# OpenBook_Schematic.net
KiCad netlist of a schematic drawn in EAGLE
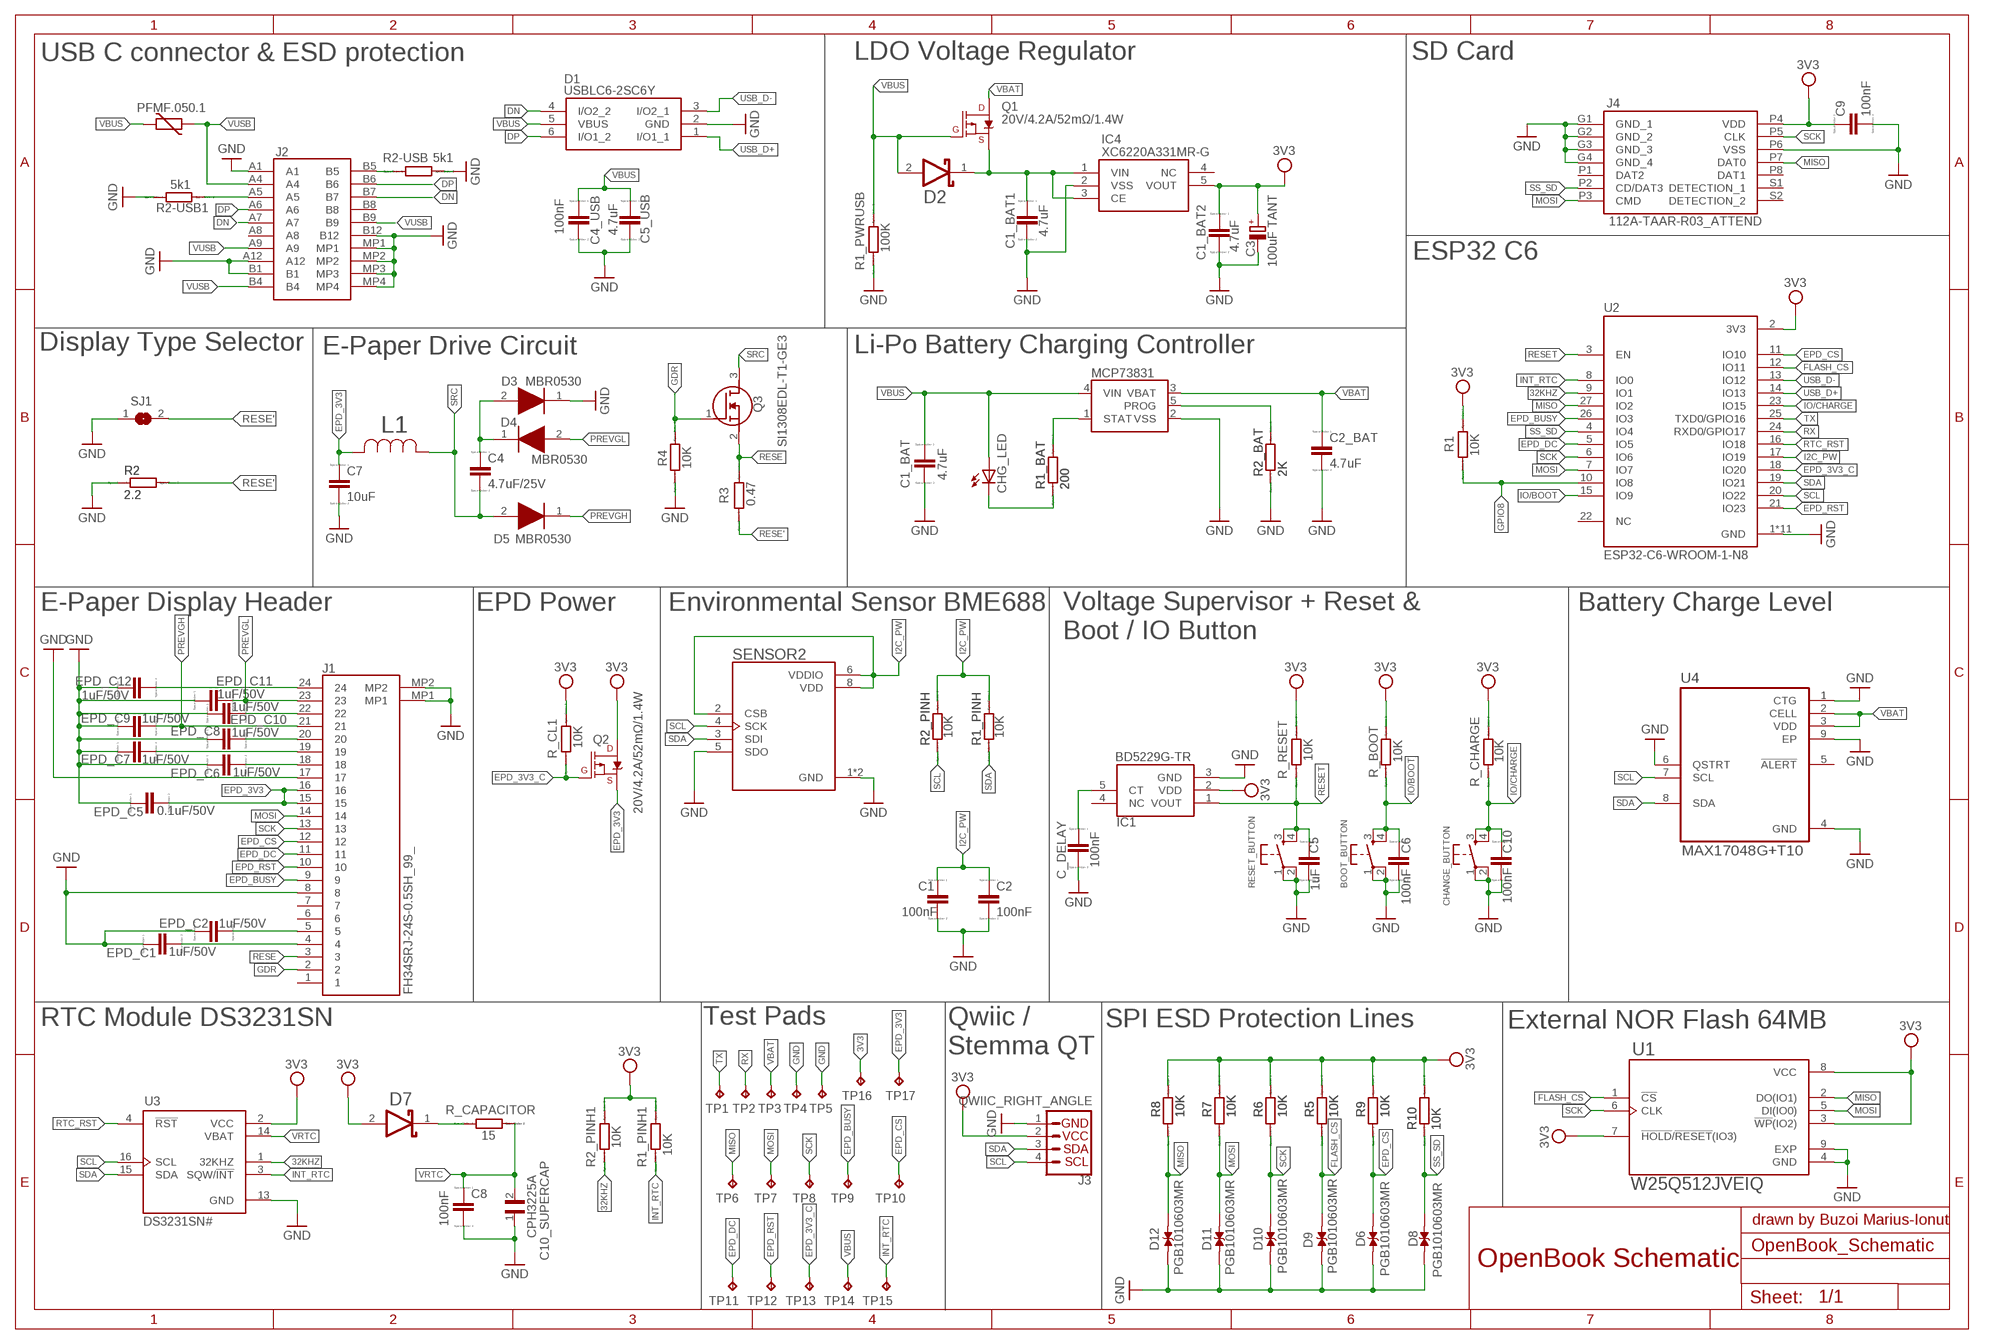
[diagram p0: schematic, sheet 1]

(export (version "E")
  (design (tool "Eeschema 10.0.6"))
  (components
    (comp (ref "C1")
      (value "100nF")
      (footprint "eagle-import:ESP32_WROVER_EAGLE-LTSPICE_C0402")
      (libsource (lib "eagle-import") (part "ESP32_WROVER_EAGLE-LTSPICE_CC0402"))
    )
    (comp (ref "C1_BAT")
      (value "4.7uF")
      (footprint "eagle-import:ESP32_WROVER_EAGLE-LTSPICE_C0402")
      (libsource (lib "eagle-import") (part "ESP32_WROVER_EAGLE-LTSPICE_CC0402"))
    )
    (comp (ref "C1_BAT1")
      (value "4.7uF")
      (footprint "eagle-import:ESP32_WROVER_EAGLE-LTSPICE_C0402")
      (libsource (lib "eagle-import") (part "ESP32_WROVER_EAGLE-LTSPICE_CC0402"))
    )
    (comp (ref "C1_BAT2")
      (value "4.7uF")
      (footprint "eagle-import:ESP32_WROVER_EAGLE-LTSPICE_C0402")
      (libsource (lib "eagle-import") (part "ESP32_WROVER_EAGLE-LTSPICE_CC0402"))
    )
    (comp (ref "C2")
      (value "100nF")
      (footprint "eagle-import:ESP32_WROVER_EAGLE-LTSPICE_C0402")
      (libsource (lib "eagle-import") (part "ESP32_WROVER_EAGLE-LTSPICE_CC0402"))
    )
    (comp (ref "C2_BAT")
      (value "4.7uF")
      (footprint "eagle-import:ESP32_WROVER_EAGLE-LTSPICE_C0402")
      (libsource (lib "eagle-import") (part "ESP32_WROVER_EAGLE-LTSPICE_CC0402"))
    )
    (comp (ref "C3")
      (value "100uF TANT")
      (footprint "eagle-import:RCL_CT3528")
      (libsource (lib "eagle-import") (part "RCL_CPOL-EUCT3528"))
    )
    (comp (ref "C4")
      (value "4.7uF/25V")
      (footprint "eagle-import:ESP32_WROVER_EAGLE-LTSPICE_C0402")
      (libsource (lib "eagle-import") (part "ESP32_WROVER_EAGLE-LTSPICE_CC0402"))
    )
    (comp (ref "C4_USB")
      (value "100nF")
      (footprint "eagle-import:ESP32_WROVER_EAGLE-LTSPICE_C0402")
      (libsource (lib "eagle-import") (part "ESP32_WROVER_EAGLE-LTSPICE_CC0402"))
    )
    (comp (ref "C5")
      (value "1uF")
      (footprint "eagle-import:ESP32_WROVER_EAGLE-LTSPICE_C0402")
      (libsource (lib "eagle-import") (part "ESP32_WROVER_EAGLE-LTSPICE_CC0402"))
    )
    (comp (ref "C5_USB")
      (value "4.7uF")
      (footprint "eagle-import:ESP32_WROVER_EAGLE-LTSPICE_C0402")
      (libsource (lib "eagle-import") (part "ESP32_WROVER_EAGLE-LTSPICE_CC0402"))
    )
    (comp (ref "C6")
      (value "100nF")
      (footprint "eagle-import:ESP32_WROVER_EAGLE-LTSPICE_C0402")
      (libsource (lib "eagle-import") (part "ESP32_WROVER_EAGLE-LTSPICE_CC0402"))
    )
    (comp (ref "C7")
      (value "10uF")
      (footprint "eagle-import:ESP32_WROVER_EAGLE-LTSPICE_C0402")
      (libsource (lib "eagle-import") (part "ESP32_WROVER_EAGLE-LTSPICE_CC0402"))
    )
    (comp (ref "C8")
      (value "100nF")
      (footprint "eagle-import:ESP32_WROVER_EAGLE-LTSPICE_C0402")
      (libsource (lib "eagle-import") (part "ESP32_WROVER_EAGLE-LTSPICE_CC0402"))
    )
    (comp (ref "C9")
      (value "100nF")
      (footprint "eagle-import:ESP32_WROVER_EAGLE-LTSPICE_C0402")
      (libsource (lib "eagle-import") (part "ESP32_WROVER_EAGLE-LTSPICE_CC0402"))
    )
    (comp (ref "C10")
      (value "100nF")
      (footprint "eagle-import:ESP32_WROVER_EAGLE-LTSPICE_C0402")
      (libsource (lib "eagle-import") (part "ESP32_WROVER_EAGLE-LTSPICE_CC0402"))
    )
    (comp (ref "C10_SUPERCAP")
      (value "CPH3225A")
      (footprint "eagle-import:CAPCP3225X100N")
      (fields (field (name "MF") "Seiko Instruments"))
      (libsource (lib "eagle-import") (part "CPH3225A"))
    )
    (comp (ref "CHANGE_BUTTON")
      (value "BUTTON_CUSYOMV1")
      (footprint "eagle-import:MYBUTTON")
      (libsource (lib "eagle-import") (part "BUTTON_CUSYOMV1"))
    )
    (comp (ref "CHG_LED")
      (value "ADAFRUIT_LEDCHIP-LED0603")
      (footprint "eagle-import:ADAFRUIT_CHIP-LED0603")
      (libsource (lib "eagle-import") (part "ADAFRUIT_LEDCHIP-LED0603"))
    )
    (comp (ref "C_DELAY")
      (value "100nF")
      (footprint "eagle-import:ESP32_WROVER_EAGLE-LTSPICE_C0402")
      (libsource (lib "eagle-import") (part "ESP32_WROVER_EAGLE-LTSPICE_CC0402"))
    )
    (comp (ref "D1")
      (value "USBLC6-2SC6Y")
      (footprint "eagle-import:SOT95P280X145-6N")
      (fields (field (name "MF") "STMicroelectronics"))
      (libsource (lib "eagle-import") (part "USBLC6-2SC6Y"))
    )
    (comp (ref "D2")
      (value "ESP32_WROVER_AVX---SD0805S020S1R0_AVX_SD0805S020S1R0_0_0AVX_SD0805S020S1R0_0_0")
      (footprint "eagle-import:ESP32_WROVER_AVX---SD0805S020S1R0_AVX_SD0805S020S1R0_0")
      (fields
        (field (name "DIGIKEY_PART_NUMBER") "478-7800-1-ND")
        (field (name "MF") "AVX")
        (field (name "MOUSER_PART_NUMBER") "581-SD0805S020S1R0")
      )
      (libsource (lib "eagle-import") (part "ESP32_WROVER_AVX---SD0805S020S1R0_AVX_SD0805S020S1R0_0_0AVX_SD0805S020S1R0_0_0"))
    )
    (comp (ref "D3")
      (value "MBR0530")
      (footprint "eagle-import:SOD3716X135N")
      (fields (field (name "MF") "ON Semiconductor"))
      (libsource (lib "eagle-import") (part "MBR0530"))
    )
    (comp (ref "D4")
      (value "MBR0530")
      (footprint "eagle-import:SOD3716X135N")
      (fields (field (name "MF") "ON Semiconductor"))
      (libsource (lib "eagle-import") (part "MBR0530"))
    )
    (comp (ref "D5")
      (value "MBR0530")
      (footprint "eagle-import:SOD3716X135N")
      (fields (field (name "MF") "ON Semiconductor"))
      (libsource (lib "eagle-import") (part "MBR0530"))
    )
    (comp (ref "D6")
      (value "PGB1010603MR")
      (footprint "eagle-import:DIOC1608X36N")
      (fields (field (name "MF") "Littelfuse Inc."))
      (libsource (lib "eagle-import") (part "PGB1010603MR"))
    )
    (comp (ref "D7")
      (value "ESP32_WROVER_AVX---SD0805S020S1R0_AVX_SD0805S020S1R0_0_0AVX_SD0805S020S1R0_0_0")
      (footprint "eagle-import:ESP32_WROVER_AVX---SD0805S020S1R0_AVX_SD0805S020S1R0_0")
      (fields
        (field (name "DIGIKEY_PART_NUMBER") "478-7800-1-ND")
        (field (name "MF") "AVX")
        (field (name "MOUSER_PART_NUMBER") "581-SD0805S020S1R0")
      )
      (libsource (lib "eagle-import") (part "ESP32_WROVER_AVX---SD0805S020S1R0_AVX_SD0805S020S1R0_0_0AVX_SD0805S020S1R0_0_0"))
    )
    (comp (ref "D8")
      (value "PGB1010603MR")
      (footprint "eagle-import:DIOC1608X36N")
      (fields (field (name "MF") "Littelfuse Inc."))
      (libsource (lib "eagle-import") (part "PGB1010603MR"))
    )
    (comp (ref "D9")
      (value "PGB1010603MR")
      (footprint "eagle-import:DIOC1608X36N")
      (fields (field (name "MF") "Littelfuse Inc."))
      (libsource (lib "eagle-import") (part "PGB1010603MR"))
    )
    (comp (ref "D10")
      (value "PGB1010603MR")
      (footprint "eagle-import:DIOC1608X36N")
      (fields (field (name "MF") "Littelfuse Inc."))
      (libsource (lib "eagle-import") (part "PGB1010603MR"))
    )
    (comp (ref "D11")
      (value "PGB1010603MR")
      (footprint "eagle-import:DIOC1608X36N")
      (fields (field (name "MF") "Littelfuse Inc."))
      (libsource (lib "eagle-import") (part "PGB1010603MR"))
    )
    (comp (ref "D12")
      (value "PGB1010603MR")
      (footprint "eagle-import:DIOC1608X36N")
      (fields (field (name "MF") "Littelfuse Inc."))
      (libsource (lib "eagle-import") (part "PGB1010603MR"))
    )
    (comp (ref "EPD_C1")
      (value "1uF/50V")
      (footprint "eagle-import:ESP32_WROVER_EAGLE-LTSPICE_C0402")
      (libsource (lib "eagle-import") (part "ESP32_WROVER_EAGLE-LTSPICE_CC0402"))
    )
    (comp (ref "EPD_C2")
      (value "1uF/50V")
      (footprint "eagle-import:ESP32_WROVER_EAGLE-LTSPICE_C0402")
      (libsource (lib "eagle-import") (part "ESP32_WROVER_EAGLE-LTSPICE_CC0402"))
    )
    (comp (ref "EPD_C5")
      (value "0.1uF/50V")
      (footprint "eagle-import:ESP32_WROVER_EAGLE-LTSPICE_C0402")
      (libsource (lib "eagle-import") (part "ESP32_WROVER_EAGLE-LTSPICE_CC0402"))
    )
    (comp (ref "EPD_C6")
      (value "1uF/50V")
      (footprint "eagle-import:ESP32_WROVER_EAGLE-LTSPICE_C0402")
      (libsource (lib "eagle-import") (part "ESP32_WROVER_EAGLE-LTSPICE_CC0402"))
    )
    (comp (ref "EPD_C7")
      (value "1uF/50V")
      (footprint "eagle-import:ESP32_WROVER_EAGLE-LTSPICE_C0402")
      (libsource (lib "eagle-import") (part "ESP32_WROVER_EAGLE-LTSPICE_CC0402"))
    )
    (comp (ref "EPD_C8")
      (value "1uF/50V")
      (footprint "eagle-import:ESP32_WROVER_EAGLE-LTSPICE_C0402")
      (libsource (lib "eagle-import") (part "ESP32_WROVER_EAGLE-LTSPICE_CC0402"))
    )
    (comp (ref "EPD_C9")
      (value "1uF/50V")
      (footprint "eagle-import:ESP32_WROVER_EAGLE-LTSPICE_C0402")
      (libsource (lib "eagle-import") (part "ESP32_WROVER_EAGLE-LTSPICE_CC0402"))
    )
    (comp (ref "EPD_C10")
      (value "1uF/50V")
      (footprint "eagle-import:ESP32_WROVER_EAGLE-LTSPICE_C0402")
      (libsource (lib "eagle-import") (part "ESP32_WROVER_EAGLE-LTSPICE_CC0402"))
    )
    (comp (ref "EPD_C11")
      (value "1uF/50V")
      (footprint "eagle-import:ESP32_WROVER_EAGLE-LTSPICE_C0402")
      (libsource (lib "eagle-import") (part "ESP32_WROVER_EAGLE-LTSPICE_CC0402"))
    )
    (comp (ref "EPD_C12")
      (value "1uF/50V")
      (footprint "eagle-import:ESP32_WROVER_EAGLE-LTSPICE_C0402")
      (libsource (lib "eagle-import") (part "ESP32_WROVER_EAGLE-LTSPICE_CC0402"))
    )
    (comp (ref "IC1")
      (value "BD5229G-TR")
      (footprint "eagle-import:SOT95P280X125-5N")
      (fields (field (name "MOUSER_PART_NUMBER") "755-BD5229G-TR"))
      (libsource (lib "eagle-import") (part "BD5229G-TR"))
    )
    (comp (ref "IC4")
      (value "XC6220A331MR-G")
      (footprint "eagle-import:SOT95P280X120-5N")
      (fields (field (name "MOUSER_PART_NUMBER") "865-XC6220A331MR-G"))
      (libsource (lib "eagle-import") (part "XC6220A331MR-G"))
    )
    (comp (ref "J1")
      (value "FH34SRJ-24S-0.5SH_99_")
      (footprint "eagle-import:FH34SRJ24S05SH99")
      (fields
        (field (name "MANUFACTURER_PART_NUMBER") "FH34SRJ-24S-0.5SH(99)")
        (field (name "MOUSER_PART_NUMBER") "798-FH34SRJ24S05SH99")
      )
      (libsource (lib "eagle-import") (part "FH34SRJ-24S-0.5SH_99_"))
    )
    (comp (ref "J2")
      (value "SAMACSYS_PARTS_USB4110-GF-A")
      (footprint "eagle-import:SAMACSYS_PARTS_USB4110GFA")
      (fields
        (field (name "MANUFACTURER_PART_NUMBER") "USB4110-GF-A")
        (field (name "MOUSER_PART_NUMBER") "640-USB4110-GF-A")
      )
      (libsource (lib "eagle-import") (part "SAMACSYS_PARTS_USB4110-GF-A"))
    )
    (comp (ref "J3")
      (value "QWIIC_RIGHT_ANGLE")
      (footprint "eagle-import:JST04_1MM_RA")
      (libsource (lib "eagle-import") (part "QWIIC_CONNECTORJS-1MM"))
    )
    (comp (ref "J4")
      (value "112A-TAAR-R03_ATTEND")
      (footprint "eagle-import:112ATAARR03ATTEND")
      (fields (field (name "MANUFACTURER_PART_NUMBER") "112A-TAAR-R03 ATTEND"))
      (libsource (lib "eagle-import") (part "112A-TAAR-R03_ATTEND"))
    )
    (comp (ref "L1")
      (value "68uH")
      (footprint "eagle-import:IND_4828-WE-TPC_WRE")
      (fields
        (field (name "MANUFACTURER_PART_NUMBER") "744043680")
        (field (name "COPYRIGHT") "Copyright (C) 2024 Ultra Librarian. All rights reserved.")
      )
      (libsource (lib "eagle-import") (part "744043680IND_4828-WE-TPC_WRE"))
    )
    (comp (ref "MCP73831")
      (value "ESP32_WROVER_SPARKFUN-IC-POWER_MCP73831")
      (footprint "eagle-import:ESP32_WROVER_SPARKFUN-IC-POWER_SOT23-5")
      (libsource (lib "eagle-import") (part "ESP32_WROVER_SPARKFUN-IC-POWER_MCP73831"))
    )
    (comp (ref "PFMF.050.1")
      (value "ESP32C6_VARISTORCN1812")
      (footprint "eagle-import:ESP32C6_VARISTOR_CT_CN1812")
      (libsource (lib "eagle-import") (part "ESP32C6_VARISTORCN1812"))
    )
    (comp (ref "Q1")
      (value "20V/4.2A/52mΩ/1.4W")
      (footprint "eagle-import:ESP32_WROVER_SPARKFUN-DISCRETESEMI_SOT23-3")
      (libsource (lib "eagle-import") (part "ESP32_WROVER_SPARKFUN-DISCRETESEMI_MOSFET_PCH-DMG2305UX-7"))
    )
    (comp (ref "Q2")
      (value "20V/4.2A/52mΩ/1.4W")
      (footprint "eagle-import:ESP32_WROVER_SPARKFUN-DISCRETESEMI_SOT23-3")
      (libsource (lib "eagle-import") (part "ESP32_WROVER_SPARKFUN-DISCRETESEMI_MOSFET_PCH-DMG2305UX-7"))
    )
    (comp (ref "Q3")
      (value "SI1308EDL-T1-GE3")
      (footprint "eagle-import:SOT65P210X110-3N")
      (fields (field (name "MF") "Vishay Siliconix"))
      (libsource (lib "eagle-import") (part "SI1308EDL-T1-GE3"))
    )
    (comp (ref "R1")
      (value "10K")
      (footprint "eagle-import:ESP32_WROVER_EAGLE-LTSPICE_R0402")
      (libsource (lib "eagle-import") (part "ESP32_WROVER_EAGLE-LTSPICE_RR0402"))
    )
    (comp (ref "R1_BAT")
      (value "200")
      (footprint "eagle-import:ESP32_WROVER_EAGLE-LTSPICE_R0402")
      (libsource (lib "eagle-import") (part "ESP32_WROVER_EAGLE-LTSPICE_RR0402"))
    )
    (comp (ref "R1_PINH")
      (value "10K")
      (footprint "eagle-import:ESP32_WROVER_EAGLE-LTSPICE_R0402")
      (libsource (lib "eagle-import") (part "ESP32_WROVER_EAGLE-LTSPICE_RR0402"))
    )
    (comp (ref "R1_PINH1")
      (value "10K")
      (footprint "eagle-import:ESP32_WROVER_EAGLE-LTSPICE_R0402")
      (libsource (lib "eagle-import") (part "ESP32_WROVER_EAGLE-LTSPICE_RR0402"))
    )
    (comp (ref "R1_PWRUSB")
      (value "100K")
      (footprint "eagle-import:ESP32_WROVER_EAGLE-LTSPICE_R0402")
      (libsource (lib "eagle-import") (part "ESP32_WROVER_EAGLE-LTSPICE_RR0402"))
    )
    (comp (ref "R2")
      (value "2.2")
      (footprint "eagle-import:ESP32_WROVER_EAGLE-LTSPICE_R0402")
      (libsource (lib "eagle-import") (part "ESP32_WROVER_EAGLE-LTSPICE_RR0402"))
    )
    (comp (ref "R2-USB")
      (value "5k1")
      (footprint "eagle-import:ESP32_WROVER_EAGLE-LTSPICE_R0402")
      (libsource (lib "eagle-import") (part "ESP32_WROVER_EAGLE-LTSPICE_RR0402"))
    )
    (comp (ref "R2-USB1")
      (value "5k1")
      (footprint "eagle-import:ESP32_WROVER_EAGLE-LTSPICE_R0402")
      (libsource (lib "eagle-import") (part "ESP32_WROVER_EAGLE-LTSPICE_RR0402"))
    )
    (comp (ref "R2_BAT")
      (value "2K")
      (footprint "eagle-import:ESP32_WROVER_EAGLE-LTSPICE_R0402")
      (libsource (lib "eagle-import") (part "ESP32_WROVER_EAGLE-LTSPICE_RR0402"))
    )
    (comp (ref "R2_PINH")
      (value "10K")
      (footprint "eagle-import:ESP32_WROVER_EAGLE-LTSPICE_R0402")
      (libsource (lib "eagle-import") (part "ESP32_WROVER_EAGLE-LTSPICE_RR0402"))
    )
    (comp (ref "R2_PINH1")
      (value "10K")
      (footprint "eagle-import:ESP32_WROVER_EAGLE-LTSPICE_R0402")
      (libsource (lib "eagle-import") (part "ESP32_WROVER_EAGLE-LTSPICE_RR0402"))
    )
    (comp (ref "R3")
      (value "0.47")
      (footprint "eagle-import:ESP32_WROVER_EAGLE-LTSPICE_R0402")
      (libsource (lib "eagle-import") (part "ESP32_WROVER_EAGLE-LTSPICE_RR0402"))
    )
    (comp (ref "R4")
      (value "10K")
      (footprint "eagle-import:ESP32_WROVER_EAGLE-LTSPICE_R0402")
      (libsource (lib "eagle-import") (part "ESP32_WROVER_EAGLE-LTSPICE_RR0402"))
    )
    (comp (ref "R5")
      (value "10K")
      (footprint "eagle-import:ESP32_WROVER_EAGLE-LTSPICE_R0402")
      (libsource (lib "eagle-import") (part "ESP32_WROVER_EAGLE-LTSPICE_RR0402"))
    )
    (comp (ref "R6")
      (value "10K")
      (footprint "eagle-import:ESP32_WROVER_EAGLE-LTSPICE_R0402")
      (libsource (lib "eagle-import") (part "ESP32_WROVER_EAGLE-LTSPICE_RR0402"))
    )
    (comp (ref "R7")
      (value "10K")
      (footprint "eagle-import:ESP32_WROVER_EAGLE-LTSPICE_R0402")
      (libsource (lib "eagle-import") (part "ESP32_WROVER_EAGLE-LTSPICE_RR0402"))
    )
    (comp (ref "R8")
      (value "10K")
      (footprint "eagle-import:ESP32_WROVER_EAGLE-LTSPICE_R0402")
      (libsource (lib "eagle-import") (part "ESP32_WROVER_EAGLE-LTSPICE_RR0402"))
    )
    (comp (ref "R9")
      (value "10K")
      (footprint "eagle-import:ESP32_WROVER_EAGLE-LTSPICE_R0402")
      (libsource (lib "eagle-import") (part "ESP32_WROVER_EAGLE-LTSPICE_RR0402"))
    )
    (comp (ref "R10")
      (value "10K")
      (footprint "eagle-import:ESP32_WROVER_EAGLE-LTSPICE_R0402")
      (libsource (lib "eagle-import") (part "ESP32_WROVER_EAGLE-LTSPICE_RR0402"))
    )
    (comp (ref "RESET_BUTTON")
      (value "BUTTON_CUSYOMV1")
      (footprint "eagle-import:MYBUTTON")
      (libsource (lib "eagle-import") (part "BUTTON_CUSYOMV1"))
    )
    (comp (ref "R_BOOT")
      (value "10K")
      (footprint "eagle-import:ESP32_WROVER_EAGLE-LTSPICE_R0402")
      (libsource (lib "eagle-import") (part "ESP32_WROVER_EAGLE-LTSPICE_RR0402"))
    )
    (comp (ref "R_CAPACITOR")
      (value "15")
      (footprint "eagle-import:ESP32_WROVER_EAGLE-LTSPICE_R0402")
      (libsource (lib "eagle-import") (part "ESP32_WROVER_EAGLE-LTSPICE_RR0402"))
    )
    (comp (ref "R_CHARGE")
      (value "10K")
      (footprint "eagle-import:ESP32_WROVER_EAGLE-LTSPICE_R0402")
      (libsource (lib "eagle-import") (part "ESP32_WROVER_EAGLE-LTSPICE_RR0402"))
    )
    (comp (ref "R_CL1")
      (value "10K")
      (footprint "eagle-import:ESP32_WROVER_EAGLE-LTSPICE_R0402")
      (libsource (lib "eagle-import") (part "ESP32_WROVER_EAGLE-LTSPICE_RR0402"))
    )
    (comp (ref "R_RESET")
      (value "10K")
      (footprint "eagle-import:ESP32_WROVER_EAGLE-LTSPICE_R0402")
      (libsource (lib "eagle-import") (part "ESP32_WROVER_EAGLE-LTSPICE_RR0402"))
    )
    (comp (ref "SENSOR2")
      (value "ESP32_WROVER_BME680_BME680")
      (footprint "eagle-import:ESP32_WROVER_BME680_PSON80P300X300X100-8N")
      (fields (field (name "MF") "Bosch Sensortec") (field (name "MP") "BME680"))
      (libsource (lib "eagle-import") (part "ESP32_WROVER_BME680_BME680"))
    )
    (comp (ref "SJ1") (value "SJ") (footprint "eagle-import:SJ") (libsource (lib "eagle-import") (part "SJ")))
    (comp (ref "TP1")
      (value "TPTP20R")
      (footprint "eagle-import:TP20R")
      (libsource (lib "eagle-import") (part "TPTP20R"))
    )
    (comp (ref "TP2")
      (value "TPTP20R")
      (footprint "eagle-import:TP20R")
      (libsource (lib "eagle-import") (part "TPTP20R"))
    )
    (comp (ref "TP3")
      (value "TPTP20R")
      (footprint "eagle-import:TP20R")
      (libsource (lib "eagle-import") (part "TPTP20R"))
    )
    (comp (ref "TP4")
      (value "TPTP20R")
      (footprint "eagle-import:TP20R")
      (libsource (lib "eagle-import") (part "TPTP20R"))
    )
    (comp (ref "TP5")
      (value "TPTP20R")
      (footprint "eagle-import:TP20R")
      (libsource (lib "eagle-import") (part "TPTP20R"))
    )
    (comp (ref "TP6")
      (value "TPTP20R")
      (footprint "eagle-import:TP20R")
      (libsource (lib "eagle-import") (part "TPTP20R"))
    )
    (comp (ref "TP7")
      (value "TPTP20R")
      (footprint "eagle-import:TP20R")
      (libsource (lib "eagle-import") (part "TPTP20R"))
    )
    (comp (ref "TP8")
      (value "TPTP20R")
      (footprint "eagle-import:TP20R")
      (libsource (lib "eagle-import") (part "TPTP20R"))
    )
    (comp (ref "TP9")
      (value "TPTP20R")
      (footprint "eagle-import:TP20R")
      (libsource (lib "eagle-import") (part "TPTP20R"))
    )
    (comp (ref "TP10")
      (value "TPTP20R")
      (footprint "eagle-import:TP20R")
      (libsource (lib "eagle-import") (part "TPTP20R"))
    )
    (comp (ref "TP11")
      (value "TPTP20R")
      (footprint "eagle-import:TP20R")
      (libsource (lib "eagle-import") (part "TPTP20R"))
    )
    (comp (ref "TP12")
      (value "TPTP20R")
      (footprint "eagle-import:TP20R")
      (libsource (lib "eagle-import") (part "TPTP20R"))
    )
    (comp (ref "TP13")
      (value "TPTP20R")
      (footprint "eagle-import:TP20R")
      (libsource (lib "eagle-import") (part "TPTP20R"))
    )
    (comp (ref "TP14")
      (value "TPTP20R")
      (footprint "eagle-import:TP20R")
      (libsource (lib "eagle-import") (part "TPTP20R"))
    )
    (comp (ref "TP15")
      (value "TPTP20R")
      (footprint "eagle-import:TP20R")
      (libsource (lib "eagle-import") (part "TPTP20R"))
    )
    (comp (ref "TP16")
      (value "TPTP20R")
      (footprint "eagle-import:TP20R")
      (libsource (lib "eagle-import") (part "TPTP20R"))
    )
    (comp (ref "TP17")
      (value "TPTP20R")
      (footprint "eagle-import:TP20R")
      (libsource (lib "eagle-import") (part "TPTP20R"))
    )
    (comp (ref "U$2")
      (value "BUTTON_CUSYOMV1")
      (footprint "eagle-import:MYBUTTON")
      (libsource (lib "eagle-import") (part "BUTTON_CUSYOMV1"))
    )
    (comp (ref "U1")
      (value "W25Q512JVEIQ")
      (footprint "eagle-import:SON127P600X800X80-9N")
      (fields (field (name "MF") "Winbond Electronics"))
      (libsource (lib "eagle-import") (part "W25Q512JVEIQ"))
    )
    (comp (ref "U2")
      (value "ESP32-C6-WROOM-1-N8")
      (footprint "eagle-import:XCVR_ESP32-C6-WROOM-1-N8")
      (fields (field (name "MF") "Espressif Systems"))
      (libsource (lib "eagle-import") (part "ESP32-C6-WROOM-1-N8"))
    )
    (comp (ref "U3")
      (value "DS3231SN#")
      (footprint "eagle-import:SOIC127P1032X265-16N")
      (fields (field (name "MF") "Analog Devices"))
      (libsource (lib "eagle-import") (part "DS3231SN#"))
    )
    (comp (ref "U4")
      (value "MAX17048G+T10")
      (footprint "eagle-import:SON50P200X200X80-9N")
      (fields (field (name "MF") "Analog Devices"))
      (libsource (lib "eagle-import") (part "MAX17048G+T10"))
    )
  )
  (nets
    (net (code "1") (name "3V3") (class "Default")
      (node (ref "C1_BAT2") (pin "1") (pinfunction "1_1") (pintype "passive"))
      (node (ref "C3") (pin "+") (pinfunction "+_+") (pintype "passive"))
      (node (ref "C9") (pin "1") (pinfunction "1_1") (pintype "passive"))
      (node (ref "D7") (pin "2") (pinfunction "ANODE_2") (pintype "bidirectional"))
      (node (ref "IC1") (pin "2") (pinfunction "VDD_2") (pintype "bidirectional"))
      (node (ref "IC4") (pin "5") (pinfunction "VOUT_5") (pintype "bidirectional"))
      (node (ref "J3") (pin "2") (pinfunction "2_2") (pintype "power_in"))
      (node (ref "J4") (pin "P4") (pinfunction "VDD_P4") (pintype "bidirectional"))
      (node (ref "Q2") (pin "3") (pinfunction "D_3") (pintype "bidirectional"))
      (node (ref "R1") (pin "2") (pinfunction "2_2") (pintype "passive"))
      (node (ref "R10") (pin "2") (pinfunction "2_2") (pintype "passive"))
      (node (ref "R1_PINH1") (pin "2") (pinfunction "2_2") (pintype "passive"))
      (node (ref "R2_PINH1") (pin "2") (pinfunction "2_2") (pintype "passive"))
      (node (ref "R5") (pin "2") (pinfunction "2_2") (pintype "passive"))
      (node (ref "R6") (pin "2") (pinfunction "2_2") (pintype "passive"))
      (node (ref "R7") (pin "2") (pinfunction "2_2") (pintype "passive"))
      (node (ref "R8") (pin "2") (pinfunction "2_2") (pintype "passive"))
      (node (ref "R9") (pin "2") (pinfunction "2_2") (pintype "passive"))
      (node (ref "R_BOOT") (pin "2") (pinfunction "2_2") (pintype "passive"))
      (node (ref "R_CHARGE") (pin "2") (pinfunction "2_2") (pintype "passive"))
      (node (ref "R_CL1") (pin "2") (pinfunction "2_2") (pintype "passive"))
      (node (ref "R_RESET") (pin "2") (pinfunction "2_2") (pintype "passive"))
      (node (ref "TP16") (pin "TP") (pinfunction "TP_TP") (pintype "input"))
      (node (ref "U1") (pin "3") (pinfunction "~{WP}(IO2)_3") (pintype "bidirectional"))
      (node (ref "U1") (pin "7") (pinfunction "~{HOLD}/~{RESET}(IO3)_7") (pintype "bidirectional"))
      (node (ref "U1") (pin "8") (pinfunction "VCC_8") (pintype "power_in"))
      (node (ref "U2") (pin "2") (pinfunction "3V3_2") (pintype "power_in"))
      (node (ref "U3") (pin "2") (pinfunction "VCC_2") (pintype "power_in"))
    )
    (net (code "2") (name "32KHZ") (class "Default")
      (node (ref "R2_PINH1") (pin "1") (pinfunction "1_1") (pintype "passive"))
      (node (ref "U2") (pin "9") (pinfunction "IO1_9") (pintype "bidirectional"))
      (node (ref "U3") (pin "1") (pinfunction "32KHZ_1") (pintype "output"))
    )
    (net (code "3") (name "DN") (class "Default")
      (node (ref "D1") (pin "4") (pinfunction "I/O2_2_4") (pintype "bidirectional"))
      (node (ref "J2") (pin "A7") (pinfunction "A7_A7") (pintype "bidirectional"))
      (node (ref "J2") (pin "B7") (pinfunction "B7_B7") (pintype "bidirectional"))
    )
    (net (code "4") (name "DP") (class "Default")
      (node (ref "D1") (pin "6") (pinfunction "I/O1_2_6") (pintype "bidirectional"))
      (node (ref "J2") (pin "A6") (pinfunction "A6_A6") (pintype "bidirectional"))
      (node (ref "J2") (pin "B6") (pinfunction "B6_B6") (pintype "bidirectional"))
    )
    (net (code "5") (name "EPD_3V3") (class "Default")
      (node (ref "C7") (pin "1") (pinfunction "1_1") (pintype "passive"))
      (node (ref "EPD_C5") (pin "2") (pinfunction "2_2") (pintype "passive"))
      (node (ref "J1") (pin "15") (pinfunction "15_15") (pintype "bidirectional"))
      (node (ref "J1") (pin "16") (pinfunction "16_16") (pintype "bidirectional"))
      (node (ref "L1") (pin "2") (pinfunction "2_2") (pintype "passive"))
      (node (ref "Q2") (pin "2") (pinfunction "S_2") (pintype "bidirectional"))
      (node (ref "TP17") (pin "TP") (pinfunction "TP_TP") (pintype "input"))
    )
    (net (code "6") (name "EPD_3V3_C") (class "Default")
      (node (ref "Q2") (pin "1") (pinfunction "G_1") (pintype "bidirectional"))
      (node (ref "R_CL1") (pin "1") (pinfunction "1_1") (pintype "passive"))
      (node (ref "TP13") (pin "TP") (pinfunction "TP_TP") (pintype "input"))
      (node (ref "U2") (pin "18") (pinfunction "IO20_18") (pintype "bidirectional"))
    )
    (net (code "7") (name "EPD_BUSY") (class "Default")
      (node (ref "J1") (pin "9") (pinfunction "9_9") (pintype "bidirectional"))
      (node (ref "TP9") (pin "TP") (pinfunction "TP_TP") (pintype "input"))
      (node (ref "U2") (pin "26") (pinfunction "IO3_26") (pintype "bidirectional"))
    )
    (net (code "8") (name "EPD_CS") (class "Default")
      (node (ref "D6") (pin "2") (pinfunction "2_2") (pintype "passive"))
      (node (ref "J1") (pin "12") (pinfunction "12_12") (pintype "bidirectional"))
      (node (ref "R9") (pin "1") (pinfunction "1_1") (pintype "passive"))
      (node (ref "TP10") (pin "TP") (pinfunction "TP_TP") (pintype "input"))
      (node (ref "U2") (pin "11") (pinfunction "IO10_11") (pintype "bidirectional"))
    )
    (net (code "9") (name "EPD_DC") (class "Default")
      (node (ref "J1") (pin "11") (pinfunction "11_11") (pintype "bidirectional"))
      (node (ref "TP11") (pin "TP") (pinfunction "TP_TP") (pintype "input"))
      (node (ref "U2") (pin "5") (pinfunction "IO5_5") (pintype "bidirectional"))
    )
    (net (code "10") (name "EPD_RST") (class "Default")
      (node (ref "J1") (pin "10") (pinfunction "10_10") (pintype "bidirectional"))
      (node (ref "TP12") (pin "TP") (pinfunction "TP_TP") (pintype "input"))
      (node (ref "U2") (pin "21") (pinfunction "IO23_21") (pintype "bidirectional"))
    )
    (net (code "11") (name "FLASH_CS") (class "Default")
      (node (ref "D9") (pin "2") (pinfunction "2_2") (pintype "passive"))
      (node (ref "R5") (pin "1") (pinfunction "1_1") (pintype "passive"))
      (node (ref "U1") (pin "1") (pinfunction "~{CS}_1") (pintype "input"))
      (node (ref "U2") (pin "12") (pinfunction "IO11_12") (pintype "bidirectional"))
    )
    (net (code "12") (name "GDR") (class "Default")
      (node (ref "J1") (pin "2") (pinfunction "2_2") (pintype "bidirectional"))
      (node (ref "Q3") (pin "1") (pinfunction "G_1") (pintype "bidirectional"))
      (node (ref "R4") (pin "2") (pinfunction "2_2") (pintype "passive"))
    )
    (net (code "13") (name "GND") (class "Default")
      (node (ref "C1") (pin "2") (pinfunction "2_2") (pintype "passive"))
      (node (ref "C10") (pin "2") (pinfunction "2_2") (pintype "passive"))
      (node (ref "C10_SUPERCAP") (pin "1") (pinfunction "1_1") (pintype "passive"))
      (node (ref "C1_BAT") (pin "2") (pinfunction "2_2") (pintype "passive"))
      (node (ref "C1_BAT1") (pin "2") (pinfunction "2_2") (pintype "passive"))
      (node (ref "C1_BAT2") (pin "2") (pinfunction "2_2") (pintype "passive"))
      (node (ref "C2") (pin "2") (pinfunction "2_2") (pintype "passive"))
      (node (ref "C2_BAT") (pin "2") (pinfunction "2_2") (pintype "passive"))
      (node (ref "C3") (pin "-") (pinfunction "-_-") (pintype "passive"))
      (node (ref "C4_USB") (pin "2") (pinfunction "2_2") (pintype "passive"))
      (node (ref "C5") (pin "2") (pinfunction "2_2") (pintype "passive"))
      (node (ref "C5_USB") (pin "2") (pinfunction "2_2") (pintype "passive"))
      (node (ref "C6") (pin "2") (pinfunction "2_2") (pintype "passive"))
      (node (ref "C7") (pin "2") (pinfunction "2_2") (pintype "passive"))
      (node (ref "C8") (pin "2") (pinfunction "2_2") (pintype "passive"))
      (node (ref "C9") (pin "2") (pinfunction "2_2") (pintype "passive"))
      (node (ref "CHANGE_BUTTON") (pin "1") (pinfunction "1_1") (pintype "passive"))
      (node (ref "CHANGE_BUTTON") (pin "2") (pinfunction "2_2") (pintype "passive"))
      (node (ref "C_DELAY") (pin "2") (pinfunction "2_2") (pintype "passive"))
      (node (ref "D1") (pin "2") (pinfunction "GND_2") (pintype "bidirectional"))
      (node (ref "D10") (pin "1") (pinfunction "1_1") (pintype "passive"))
      (node (ref "D11") (pin "1") (pinfunction "1_1") (pintype "passive"))
      (node (ref "D12") (pin "1") (pinfunction "1_1") (pintype "passive"))
      (node (ref "D3") (pin "1") (pinfunction "K_1") (pintype "bidirectional"))
      (node (ref "D6") (pin "1") (pinfunction "1_1") (pintype "passive"))
      (node (ref "D8") (pin "1") (pinfunction "1_1") (pintype "passive"))
      (node (ref "D9") (pin "1") (pinfunction "1_1") (pintype "passive"))
      (node (ref "EPD_C1") (pin "1") (pinfunction "1_1") (pintype "passive"))
      (node (ref "EPD_C10") (pin "1") (pinfunction "1_1") (pintype "passive"))
      (node (ref "EPD_C11") (pin "1") (pinfunction "1_1") (pintype "passive"))
      (node (ref "EPD_C12") (pin "1") (pinfunction "1_1") (pintype "passive"))
      (node (ref "EPD_C2") (pin "1") (pinfunction "1_1") (pintype "passive"))
      (node (ref "EPD_C5") (pin "1") (pinfunction "1_1") (pintype "passive"))
      (node (ref "EPD_C6") (pin "1") (pinfunction "1_1") (pintype "passive"))
      (node (ref "EPD_C7") (pin "1") (pinfunction "1_1") (pintype "passive"))
      (node (ref "EPD_C8") (pin "1") (pinfunction "1_1") (pintype "passive"))
      (node (ref "EPD_C9") (pin "1") (pinfunction "1_1") (pintype "passive"))
      (node (ref "IC1") (pin "3") (pinfunction "GND_3") (pintype "bidirectional"))
      (node (ref "IC4") (pin "2") (pinfunction "VSS_2") (pintype "bidirectional"))
      (node (ref "J1") (pin "17") (pinfunction "17_17") (pintype "bidirectional"))
      (node (ref "J1") (pin "8") (pinfunction "8_8") (pintype "bidirectional"))
      (node (ref "J1") (pin "MP1") (pinfunction "MP1_MP1") (pintype "bidirectional"))
      (node (ref "J1") (pin "MP2") (pinfunction "MP2_MP2") (pintype "bidirectional"))
      (node (ref "J2") (pin "A1") (pinfunction "A1_A1") (pintype "bidirectional"))
      (node (ref "J2") (pin "A12") (pinfunction "A12_A12") (pintype "bidirectional"))
      (node (ref "J2") (pin "B1") (pinfunction "B1_B1") (pintype "bidirectional"))
      (node (ref "J2") (pin "B12") (pinfunction "B12_B12") (pintype "bidirectional"))
      (node (ref "J2") (pin "MP1") (pinfunction "MP1_MP1") (pintype "bidirectional"))
      (node (ref "J2") (pin "MP2") (pinfunction "MP2_MP2") (pintype "bidirectional"))
      (node (ref "J2") (pin "MP3") (pinfunction "MP3_MP3") (pintype "bidirectional"))
      (node (ref "J2") (pin "MP4") (pinfunction "MP4_MP4") (pintype "bidirectional"))
      (node (ref "J3") (pin "1") (pinfunction "1_1") (pintype "power_in"))
      (node (ref "J4") (pin "G1") (pinfunction "GND_1_G1") (pintype "bidirectional"))
      (node (ref "J4") (pin "G2") (pinfunction "GND_2_G2") (pintype "bidirectional"))
      (node (ref "J4") (pin "G3") (pinfunction "GND_3_G3") (pintype "bidirectional"))
      (node (ref "J4") (pin "G4") (pinfunction "GND_4_G4") (pintype "bidirectional"))
      (node (ref "J4") (pin "P6") (pinfunction "VSS_P6") (pintype "bidirectional"))
      (node (ref "MCP73831") (pin "2") (pinfunction "VSS_2") (pintype "power_in"))
      (node (ref "R1_PWRUSB") (pin "1") (pinfunction "1_1") (pintype "passive"))
      (node (ref "R2") (pin "1") (pinfunction "1_1") (pintype "passive"))
      (node (ref "R2-USB") (pin "2") (pinfunction "2_2") (pintype "passive"))
      (node (ref "R2-USB1") (pin "1") (pinfunction "1_1") (pintype "passive"))
      (node (ref "R2_BAT") (pin "1") (pinfunction "1_1") (pintype "passive"))
      (node (ref "R4") (pin "1") (pinfunction "1_1") (pintype "passive"))
      (node (ref "RESET_BUTTON") (pin "1") (pinfunction "1_1") (pintype "passive"))
      (node (ref "RESET_BUTTON") (pin "2") (pinfunction "2_2") (pintype "passive"))
      (node (ref "SENSOR2") (pin "1") (pinfunction "GND_1") (pintype "power_in"))
      (node (ref "SENSOR2") (pin "5") (pinfunction "SDO_5") (pintype "bidirectional"))
      (node (ref "SENSOR2") (pin "7") (pinfunction "GND_7") (pintype "power_in"))
      (node (ref "SJ1") (pin "1") (pinfunction "1_1") (pintype "passive"))
      (node (ref "TP4") (pin "TP") (pinfunction "TP_TP") (pintype "input"))
      (node (ref "TP5") (pin "TP") (pinfunction "TP_TP") (pintype "input"))
      (node (ref "U$2") (pin "1") (pinfunction "1_1") (pintype "passive"))
      (node (ref "U$2") (pin "2") (pinfunction "2_2") (pintype "passive"))
      (node (ref "U1") (pin "4") (pinfunction "GND_4") (pintype "power_in"))
      (node (ref "U1") (pin "9") (pinfunction "EXP_9") (pintype "passive"))
      (node (ref "U2") (pin "1") (pinfunction "GND_1") (pintype "power_in"))
      (node (ref "U2") (pin "28") (pinfunction "GND_28") (pintype "power_in"))
      (node (ref "U2") (pin "29_1") (pinfunction "GND_29_1") (pintype "power_in"))
      (node (ref "U2") (pin "29_2") (pinfunction "GND_29_2") (pintype "power_in"))
      (node (ref "U2") (pin "29_3") (pinfunction "GND_29_3") (pintype "power_in"))
      (node (ref "U2") (pin "29_4") (pinfunction "GND_29_4") (pintype "power_in"))
      (node (ref "U2") (pin "29_5") (pinfunction "GND_29_5") (pintype "power_in"))
      (node (ref "U2") (pin "29_6") (pinfunction "GND_29_6") (pintype "power_in"))
      (node (ref "U2") (pin "29_7") (pinfunction "GND_29_7") (pintype "power_in"))
      (node (ref "U2") (pin "29_8") (pinfunction "GND_29_8") (pintype "power_in"))
      (node (ref "U2") (pin "29_9") (pinfunction "GND_29_9") (pintype "power_in"))
      (node (ref "U3") (pin "13") (pinfunction "GND_13") (pintype "power_in"))
      (node (ref "U4") (pin "1") (pinfunction "CTG_1") (pintype "power_in"))
      (node (ref "U4") (pin "4") (pinfunction "GND_4") (pintype "power_in"))
      (node (ref "U4") (pin "6") (pinfunction "QSTRT_6") (pintype "input"))
      (node (ref "U4") (pin "9") (pinfunction "EP_9") (pintype "power_in"))
    )
    (net (code "14") (name "GPIO8") (class "Default")
      (node (ref "R1") (pin "1") (pinfunction "1_1") (pintype "passive"))
      (node (ref "U2") (pin "10") (pinfunction "IO8_10") (pintype "bidirectional"))
    )
    (net (code "15") (name "I2C_PW") (class "Default")
      (node (ref "C1") (pin "1") (pinfunction "1_1") (pintype "passive"))
      (node (ref "C2") (pin "1") (pinfunction "1_1") (pintype "passive"))
      (node (ref "R1_PINH") (pin "2") (pinfunction "2_2") (pintype "passive"))
      (node (ref "R2_PINH") (pin "2") (pinfunction "2_2") (pintype "passive"))
      (node (ref "SENSOR2") (pin "2") (pinfunction "CSB_2") (pintype "input"))
      (node (ref "SENSOR2") (pin "6") (pinfunction "VDDIO_6") (pintype "power_in"))
      (node (ref "SENSOR2") (pin "8") (pinfunction "VDD_8") (pintype "power_in"))
      (node (ref "U2") (pin "17") (pinfunction "IO19_17") (pintype "bidirectional"))
    )
    (net (code "16") (name "INT_RTC") (class "Default")
      (node (ref "R1_PINH1") (pin "1") (pinfunction "1_1") (pintype "passive"))
      (node (ref "TP15") (pin "TP") (pinfunction "TP_TP") (pintype "input"))
      (node (ref "U2") (pin "8") (pinfunction "IO0_8") (pintype "bidirectional"))
      (node (ref "U3") (pin "3") (pinfunction "SQW/~{INT}_3") (pintype "output"))
    )
    (net (code "17") (name "IO{slash}BOOT") (class "Default")
      (node (ref "C6") (pin "1") (pinfunction "1_1") (pintype "passive"))
      (node (ref "R_BOOT") (pin "1") (pinfunction "1_1") (pintype "passive"))
      (node (ref "U$2") (pin "3") (pinfunction "3_3") (pintype "passive"))
      (node (ref "U$2") (pin "4") (pinfunction "4_4") (pintype "passive"))
      (node (ref "U2") (pin "15") (pinfunction "IO9_15") (pintype "bidirectional"))
    )
    (net (code "18") (name "IO{slash}CHARGE") (class "Default")
      (node (ref "C10") (pin "1") (pinfunction "1_1") (pintype "passive"))
      (node (ref "CHANGE_BUTTON") (pin "3") (pinfunction "3_3") (pintype "passive"))
      (node (ref "CHANGE_BUTTON") (pin "4") (pinfunction "4_4") (pintype "passive"))
      (node (ref "R_CHARGE") (pin "1") (pinfunction "1_1") (pintype "passive"))
      (node (ref "U2") (pin "23") (pinfunction "IO15_23") (pintype "bidirectional"))
    )
    (net (code "19") (name "MISO") (class "Default")
      (node (ref "D12") (pin "2") (pinfunction "2_2") (pintype "passive"))
      (node (ref "J4") (pin "P7") (pinfunction "DAT0_P7") (pintype "bidirectional"))
      (node (ref "R8") (pin "1") (pinfunction "1_1") (pintype "passive"))
      (node (ref "TP6") (pin "TP") (pinfunction "TP_TP") (pintype "input"))
      (node (ref "U1") (pin "2") (pinfunction "DO(IO1)_2") (pintype "bidirectional"))
      (node (ref "U2") (pin "27") (pinfunction "IO2_27") (pintype "bidirectional"))
    )
    (net (code "20") (name "MOSI") (class "Default")
      (node (ref "D11") (pin "2") (pinfunction "2_2") (pintype "passive"))
      (node (ref "J1") (pin "14") (pinfunction "14_14") (pintype "bidirectional"))
      (node (ref "J4") (pin "P3") (pinfunction "CMD_P3") (pintype "bidirectional"))
      (node (ref "R7") (pin "1") (pinfunction "1_1") (pintype "passive"))
      (node (ref "TP7") (pin "TP") (pinfunction "TP_TP") (pintype "input"))
      (node (ref "U1") (pin "5") (pinfunction "DI(IO0)_5") (pintype "bidirectional"))
      (node (ref "U2") (pin "7") (pinfunction "IO7_7") (pintype "bidirectional"))
    )
    (net (code "21") (name "Net-(CHG_LED-PadC)") (class "Default")
      (node (ref "CHG_LED") (pin "C") (pinfunction "C_C") (pintype "passive"))
      (node (ref "R1_BAT") (pin "1") (pinfunction "1_1") (pintype "passive"))
    )
    (net (code "22") (name "Net-(D2-CATHODE)") (class "Default")
      (node (ref "C1_BAT1") (pin "1") (pinfunction "1_1") (pintype "passive"))
      (node (ref "D2") (pin "1") (pinfunction "CATHODE_1") (pintype "bidirectional"))
      (node (ref "IC4") (pin "1") (pinfunction "VIN_1") (pintype "bidirectional"))
      (node (ref "IC4") (pin "3") (pinfunction "CE_3") (pintype "bidirectional"))
      (node (ref "Q1") (pin "2") (pinfunction "S_2") (pintype "bidirectional"))
    )
    (net (code "23") (name "Net-(D3-A)") (class "Default")
      (node (ref "C4") (pin "1") (pinfunction "1_1") (pintype "passive"))
      (node (ref "D3") (pin "2") (pinfunction "A_2") (pintype "bidirectional"))
      (node (ref "D4") (pin "1") (pinfunction "K_1") (pintype "bidirectional"))
    )
    (net (code "24") (name "Net-(D7-CATHODE)") (class "Default")
      (node (ref "D7") (pin "1") (pinfunction "CATHODE_1") (pintype "bidirectional"))
      (node (ref "R_CAPACITOR") (pin "1") (pinfunction "1_1") (pintype "passive"))
    )
    (net (code "25") (name "Net-(EPD_C1-Pad2)") (class "Default")
      (node (ref "EPD_C1") (pin "2") (pinfunction "2_2") (pintype "passive"))
      (node (ref "J1") (pin "4") (pinfunction "4_4") (pintype "bidirectional"))
    )
    (net (code "26") (name "Net-(EPD_C2-Pad2)") (class "Default")
      (node (ref "EPD_C2") (pin "2") (pinfunction "2_2") (pintype "passive"))
      (node (ref "J1") (pin "5") (pinfunction "5_5") (pintype "bidirectional"))
    )
    (net (code "27") (name "Net-(EPD_C6-Pad2)") (class "Default")
      (node (ref "EPD_C6") (pin "2") (pinfunction "2_2") (pintype "passive"))
      (node (ref "J1") (pin "18") (pinfunction "18_18") (pintype "bidirectional"))
    )
    (net (code "28") (name "Net-(EPD_C7-Pad2)") (class "Default")
      (node (ref "EPD_C7") (pin "2") (pinfunction "2_2") (pintype "passive"))
      (node (ref "J1") (pin "19") (pinfunction "19_19") (pintype "bidirectional"))
    )
    (net (code "29") (name "Net-(EPD_C8-Pad2)") (class "Default")
      (node (ref "EPD_C8") (pin "2") (pinfunction "2_2") (pintype "passive"))
      (node (ref "J1") (pin "20") (pinfunction "20_20") (pintype "bidirectional"))
    )
    (net (code "30") (name "Net-(EPD_C10-Pad2)") (class "Default")
      (node (ref "EPD_C10") (pin "2") (pinfunction "2_2") (pintype "passive"))
      (node (ref "J1") (pin "22") (pinfunction "22_22") (pintype "bidirectional"))
    )
    (net (code "31") (name "Net-(EPD_C12-Pad2)") (class "Default")
      (node (ref "EPD_C12") (pin "2") (pinfunction "2_2") (pintype "passive"))
      (node (ref "J1") (pin "24") (pinfunction "24_24") (pintype "bidirectional"))
    )
    (net (code "32") (name "Net-(IC1-CT)") (class "Default")
      (node (ref "C_DELAY") (pin "1") (pinfunction "1_1") (pintype "passive"))
      (node (ref "IC1") (pin "5") (pinfunction "CT_5") (pintype "bidirectional"))
    )
    (net (code "33") (name "Net-(J2-PadA5)") (class "Default")
      (node (ref "J2") (pin "A5") (pinfunction "A5_A5") (pintype "bidirectional"))
      (node (ref "R2-USB1") (pin "2") (pinfunction "2_2") (pintype "passive"))
    )
    (net (code "34") (name "Net-(J2-PadB5)") (class "Default")
      (node (ref "J2") (pin "B5") (pinfunction "B5_B5") (pintype "bidirectional"))
      (node (ref "R2-USB") (pin "1") (pinfunction "1_1") (pintype "passive"))
    )
    (net (code "35") (name "Net-(MCP73831-PROG)") (class "Default")
      (node (ref "MCP73831") (pin "5") (pinfunction "PROG_5") (pintype "input"))
      (node (ref "R2_BAT") (pin "2") (pinfunction "2_2") (pintype "passive"))
    )
    (net (code "36") (name "Net-(MCP73831-STAT)") (class "Default")
      (node (ref "MCP73831") (pin "1") (pinfunction "STAT_1") (pintype "output"))
      (node (ref "R1_BAT") (pin "2") (pinfunction "2_2") (pintype "passive"))
    )
    (net (code "37") (name "PREVGH") (class "Default")
      (node (ref "D5") (pin "1") (pinfunction "K_1") (pintype "bidirectional"))
      (node (ref "EPD_C9") (pin "2") (pinfunction "2_2") (pintype "passive"))
      (node (ref "J1") (pin "21") (pinfunction "21_21") (pintype "bidirectional"))
    )
    (net (code "38") (name "PREVGL") (class "Default")
      (node (ref "D4") (pin "2") (pinfunction "A_2") (pintype "bidirectional"))
      (node (ref "EPD_C11") (pin "2") (pinfunction "2_2") (pintype "passive"))
      (node (ref "J1") (pin "23") (pinfunction "23_23") (pintype "bidirectional"))
    )
    (net (code "39") (name "RESE") (class "Default")
      (node (ref "J1") (pin "3") (pinfunction "3_3") (pintype "bidirectional"))
      (node (ref "Q3") (pin "2") (pinfunction "S_2") (pintype "bidirectional"))
      (node (ref "R3") (pin "2") (pinfunction "2_2") (pintype "passive"))
    )
    (net (code "40") (name "RESE'") (class "Default")
      (node (ref "R2") (pin "2") (pinfunction "2_2") (pintype "passive"))
      (node (ref "R3") (pin "1") (pinfunction "1_1") (pintype "passive"))
      (node (ref "SJ1") (pin "2") (pinfunction "2_2") (pintype "passive"))
    )
    (net (code "41") (name "RESET") (class "Default")
      (node (ref "C5") (pin "1") (pinfunction "1_1") (pintype "passive"))
      (node (ref "IC1") (pin "1") (pinfunction "VOUT_1") (pintype "bidirectional"))
      (node (ref "RESET_BUTTON") (pin "3") (pinfunction "3_3") (pintype "passive"))
      (node (ref "RESET_BUTTON") (pin "4") (pinfunction "4_4") (pintype "passive"))
      (node (ref "R_RESET") (pin "1") (pinfunction "1_1") (pintype "passive"))
      (node (ref "U2") (pin "3") (pinfunction "EN_3") (pintype "input"))
    )
    (net (code "42") (name "RTC_RST") (class "Default")
      (node (ref "U2") (pin "16") (pinfunction "IO18_16") (pintype "bidirectional"))
      (node (ref "U3") (pin "4") (pinfunction "~{RST}_4") (pintype "input"))
    )
    (net (code "43") (name "RX") (class "Default")
      (node (ref "TP2") (pin "TP") (pinfunction "TP_TP") (pintype "input"))
      (node (ref "U2") (pin "24") (pinfunction "RXD0/GPIO17_24") (pintype "bidirectional"))
    )
    (net (code "44") (name "SCK") (class "Default")
      (node (ref "D10") (pin "2") (pinfunction "2_2") (pintype "passive"))
      (node (ref "J1") (pin "13") (pinfunction "13_13") (pintype "bidirectional"))
      (node (ref "J4") (pin "P5") (pinfunction "CLK_P5") (pintype "bidirectional"))
      (node (ref "R6") (pin "1") (pinfunction "1_1") (pintype "passive"))
      (node (ref "TP8") (pin "TP") (pinfunction "TP_TP") (pintype "input"))
      (node (ref "U1") (pin "6") (pinfunction "CLK_6") (pintype "input"))
      (node (ref "U2") (pin "6") (pinfunction "IO6_6") (pintype "bidirectional"))
    )
    (net (code "45") (name "SCL") (class "Default")
      (node (ref "J3") (pin "4") (pinfunction "4_4") (pintype "passive"))
      (node (ref "R2_PINH") (pin "1") (pinfunction "1_1") (pintype "passive"))
      (node (ref "SENSOR2") (pin "4") (pinfunction "SCK_4") (pintype "input"))
      (node (ref "U2") (pin "20") (pinfunction "IO22_20") (pintype "bidirectional"))
      (node (ref "U3") (pin "16") (pinfunction "SCL_16") (pintype "input"))
      (node (ref "U4") (pin "7") (pinfunction "SCL_7") (pintype "input"))
    )
    (net (code "46") (name "SDA") (class "Default")
      (node (ref "J3") (pin "3") (pinfunction "3_3") (pintype "passive"))
      (node (ref "R1_PINH") (pin "1") (pinfunction "1_1") (pintype "passive"))
      (node (ref "SENSOR2") (pin "3") (pinfunction "SDI_3") (pintype "bidirectional"))
      (node (ref "U2") (pin "19") (pinfunction "IO21_19") (pintype "bidirectional"))
      (node (ref "U3") (pin "15") (pinfunction "SDA_15") (pintype "bidirectional"))
      (node (ref "U4") (pin "8") (pinfunction "SDA_8") (pintype "bidirectional"))
    )
    (net (code "47") (name "SRC") (class "Default")
      (node (ref "C4") (pin "2") (pinfunction "2_2") (pintype "passive"))
      (node (ref "D5") (pin "2") (pinfunction "A_2") (pintype "bidirectional"))
      (node (ref "L1") (pin "1") (pinfunction "1_1") (pintype "passive"))
      (node (ref "Q3") (pin "3") (pinfunction "D_3") (pintype "bidirectional"))
    )
    (net (code "48") (name "SS_SD") (class "Default")
      (node (ref "D8") (pin "2") (pinfunction "2_2") (pintype "passive"))
      (node (ref "J4") (pin "P2") (pinfunction "CD/DAT3_P2") (pintype "bidirectional"))
      (node (ref "R10") (pin "1") (pinfunction "1_1") (pintype "passive"))
      (node (ref "U2") (pin "4") (pinfunction "IO4_4") (pintype "bidirectional"))
    )
    (net (code "49") (name "TX") (class "Default")
      (node (ref "TP1") (pin "TP") (pinfunction "TP_TP") (pintype "input"))
      (node (ref "U2") (pin "25") (pinfunction "TXD0/GPIO16_25") (pintype "bidirectional"))
    )
    (net (code "50") (name "USB_D+") (class "Default")
      (node (ref "D1") (pin "1") (pinfunction "I/O1_1_1") (pintype "bidirectional"))
      (node (ref "U2") (pin "14") (pinfunction "IO13_14") (pintype "bidirectional"))
    )
    (net (code "51") (name "USB_D-") (class "Default")
      (node (ref "D1") (pin "3") (pinfunction "I/O2_1_3") (pintype "bidirectional"))
      (node (ref "U2") (pin "13") (pinfunction "IO12_13") (pintype "bidirectional"))
    )
    (net (code "52") (name "VBAT") (class "Default")
      (node (ref "C2_BAT") (pin "1") (pinfunction "1_1") (pintype "passive"))
      (node (ref "MCP73831") (pin "3") (pinfunction "VBAT_3") (pintype "power_in"))
      (node (ref "Q1") (pin "3") (pinfunction "D_3") (pintype "bidirectional"))
      (node (ref "TP3") (pin "TP") (pinfunction "TP_TP") (pintype "input"))
      (node (ref "U4") (pin "2") (pinfunction "CELL_2") (pintype "power_in"))
      (node (ref "U4") (pin "3") (pinfunction "VDD_3") (pintype "power_in"))
    )
    (net (code "53") (name "VBUS") (class "Default")
      (node (ref "C1_BAT") (pin "1") (pinfunction "1_1") (pintype "passive"))
      (node (ref "C4_USB") (pin "1") (pinfunction "1_1") (pintype "passive"))
      (node (ref "C5_USB") (pin "1") (pinfunction "1_1") (pintype "passive"))
      (node (ref "CHG_LED") (pin "A") (pinfunction "A_A") (pintype "passive"))
      (node (ref "D1") (pin "5") (pinfunction "VBUS_5") (pintype "bidirectional"))
      (node (ref "D2") (pin "2") (pinfunction "ANODE_2") (pintype "bidirectional"))
      (node (ref "MCP73831") (pin "4") (pinfunction "VIN_4") (pintype "power_in"))
      (node (ref "PFMF.050.1") (pin "2") (pinfunction "2_2") (pintype "passive"))
      (node (ref "Q1") (pin "1") (pinfunction "G_1") (pintype "bidirectional"))
      (node (ref "R1_PWRUSB") (pin "2") (pinfunction "2_2") (pintype "passive"))
      (node (ref "TP14") (pin "TP") (pinfunction "TP_TP") (pintype "input"))
    )
    (net (code "54") (name "VRTC") (class "Default")
      (node (ref "C10_SUPERCAP") (pin "2") (pinfunction "2_2") (pintype "passive"))
      (node (ref "C8") (pin "1") (pinfunction "1_1") (pintype "passive"))
      (node (ref "R_CAPACITOR") (pin "2") (pinfunction "2_2") (pintype "passive"))
      (node (ref "U3") (pin "14") (pinfunction "VBAT_14") (pintype "power_in"))
    )
    (net (code "55") (name "VUSB") (class "Default")
      (node (ref "J2") (pin "A4") (pinfunction "A4_A4") (pintype "bidirectional"))
      (node (ref "J2") (pin "A9") (pinfunction "A9_A9") (pintype "bidirectional"))
      (node (ref "J2") (pin "B4") (pinfunction "B4_B4") (pintype "bidirectional"))
      (node (ref "J2") (pin "B9") (pinfunction "B9_B9") (pintype "bidirectional"))
      (node (ref "PFMF.050.1") (pin "1") (pinfunction "1_1") (pintype "passive"))
    )
    (net (code "56") (name "unconnected-(IC1-NC-Pad4)") (class "Default")
      (node (ref "IC1") (pin "4") (pinfunction "NC_4") (pintype "no_connect"))
    )
    (net (code "57") (name "unconnected-(IC4-NC-Pad4)") (class "Default")
      (node (ref "IC4") (pin "4") (pinfunction "NC_4") (pintype "no_connect"))
    )
    (net (code "58") (name "unconnected-(J1-Pad1)") (class "Default")
      (node (ref "J1") (pin "1") (pinfunction "1_1") (pintype "bidirectional"))
    )
    (net (code "59") (name "unconnected-(J1-Pad6)") (class "Default")
      (node (ref "J1") (pin "6") (pinfunction "6_6") (pintype "bidirectional"))
    )
    (net (code "60") (name "unconnected-(J1-Pad7)") (class "Default")
      (node (ref "J1") (pin "7") (pinfunction "7_7") (pintype "bidirectional"))
    )
    (net (code "61") (name "unconnected-(J2-PadA8)") (class "Default")
      (node (ref "J2") (pin "A8") (pinfunction "A8_A8") (pintype "bidirectional"))
    )
    (net (code "62") (name "unconnected-(J2-PadB8)") (class "Default")
      (node (ref "J2") (pin "B8") (pinfunction "B8_B8") (pintype "bidirectional"))
    )
    (net (code "63") (name "unconnected-(J4-DAT1-PadP8)") (class "Default")
      (node (ref "J4") (pin "P8") (pinfunction "DAT1_P8") (pintype "bidirectional"))
    )
    (net (code "64") (name "unconnected-(J4-DAT2-PadP1)") (class "Default")
      (node (ref "J4") (pin "P1") (pinfunction "DAT2_P1") (pintype "bidirectional"))
    )
    (net (code "65") (name "unconnected-(J4-DETECTION_1-PadS1)") (class "Default")
      (node (ref "J4") (pin "S1") (pinfunction "DETECTION_1_S1") (pintype "bidirectional"))
    )
    (net (code "66") (name "unconnected-(J4-DETECTION_2-PadS2)") (class "Default")
      (node (ref "J4") (pin "S2") (pinfunction "DETECTION_2_S2") (pintype "bidirectional"))
    )
    (net (code "67") (name "unconnected-(U2-NC-Pad22)") (class "Default")
      (node (ref "U2") (pin "22") (pinfunction "NC_22") (pintype "no_connect"))
    )
    (net (code "68") (name "unconnected-(U4-~{ALERT}-Pad5)") (class "Default")
      (node (ref "U4") (pin "5") (pinfunction "~{ALERT}_5") (pintype "output"))
    )
  )
)
